# Wire_Puzzle.net
KiCad netlist of a schematic drawn in EAGLE
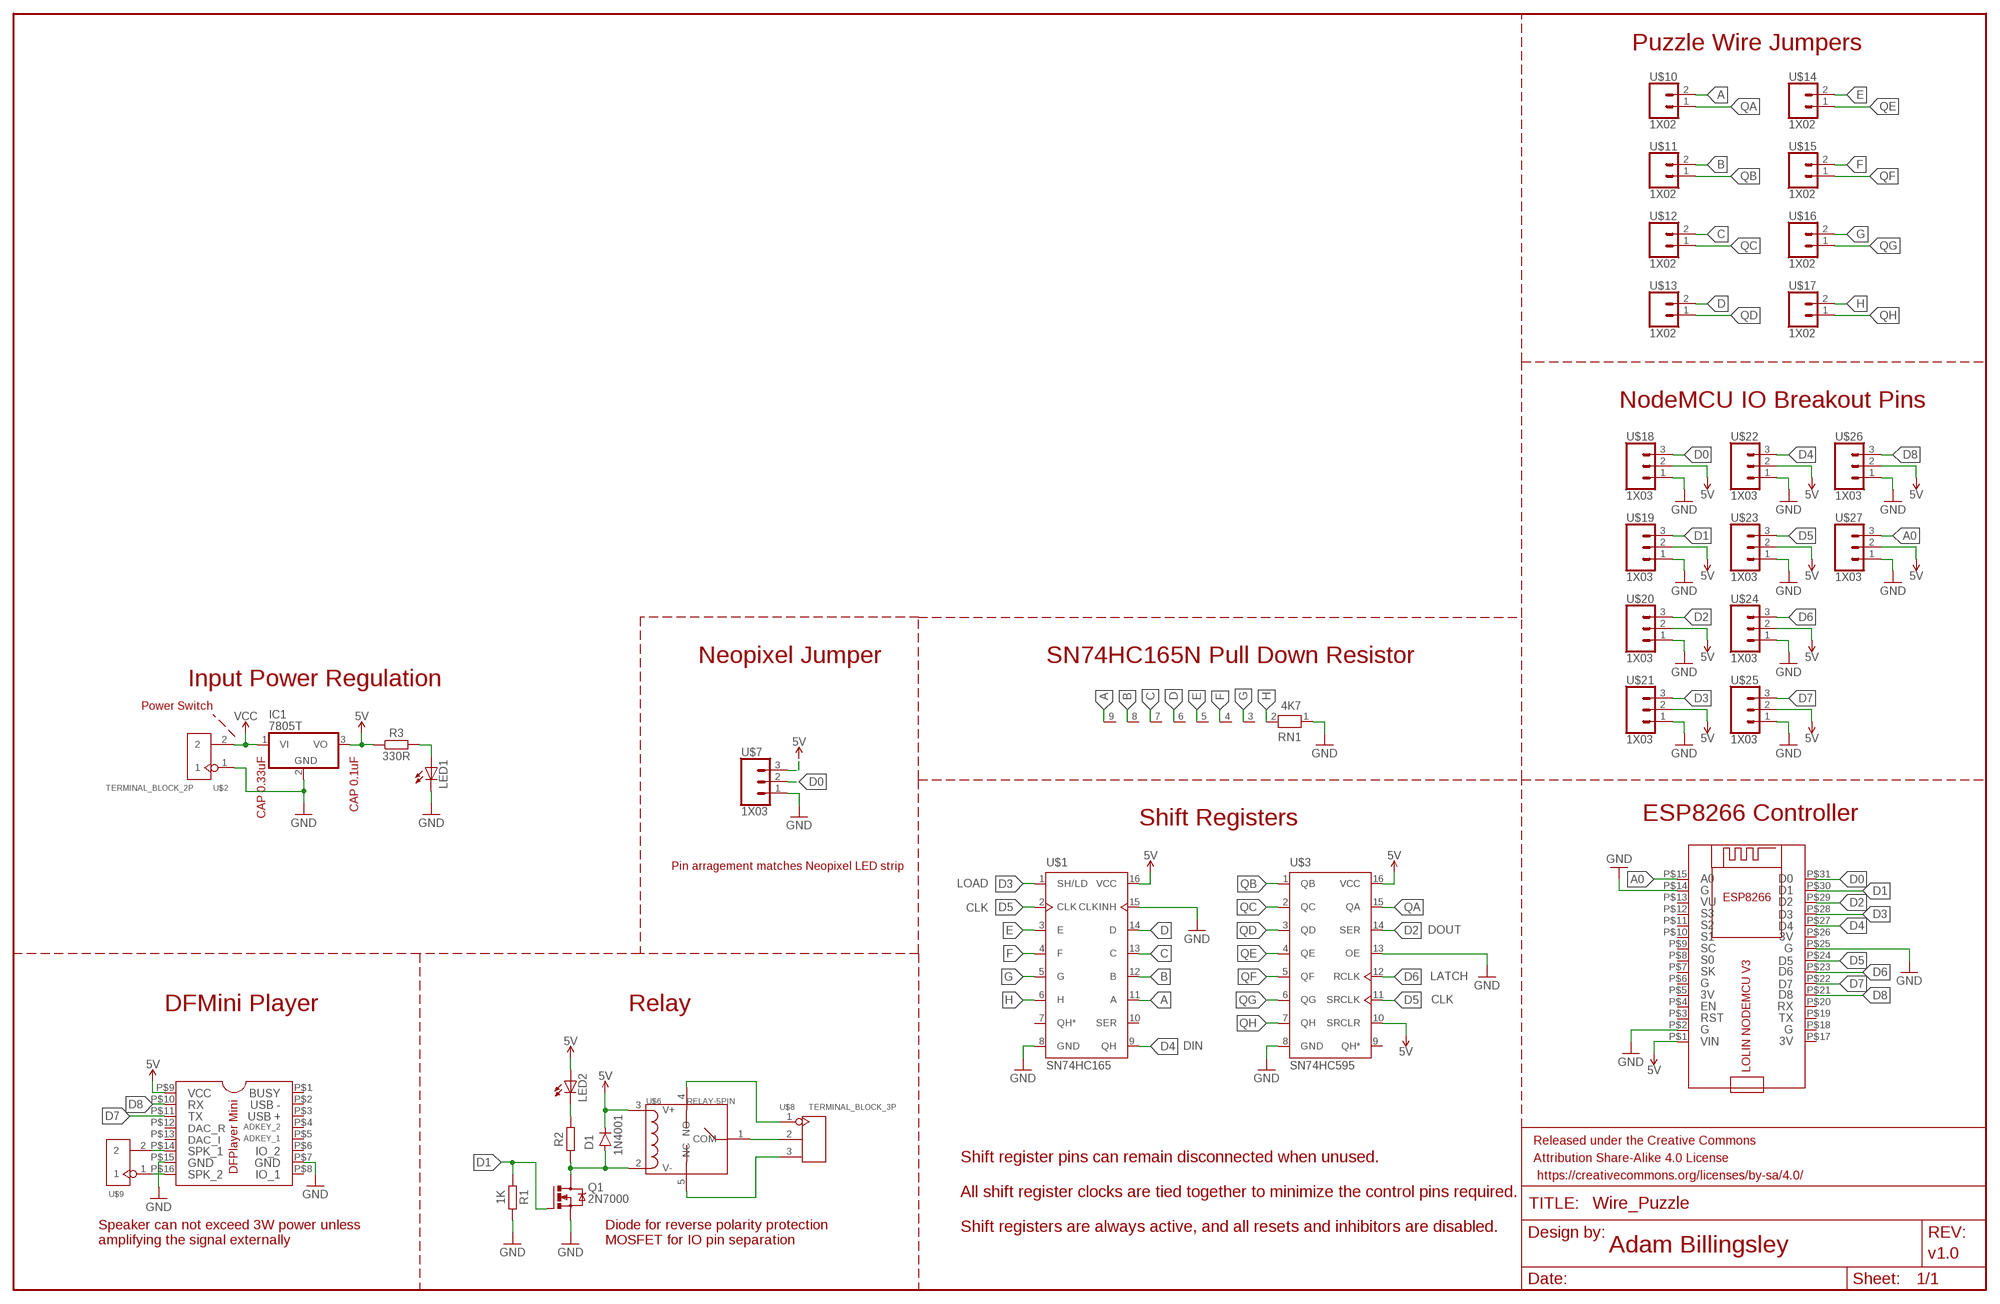
[diagram p0: schematic, sheet 1]

(export (version "E")
  (design (tool "Eeschema 10.0.6"))
  (components
    (comp (ref "D1")
      (value "1N4001")
      (footprint "eagle-import:DO-41")
      (fields
        (field (name "DIGIKEY_PART_NUMBER") "1N4004MSCT-ND")
        (field (name "MANUFACTURER") "Micro Commercial Co")
        (field (name "MPN") "1N4004")
        (field (name "CREATED_BY") "PCBLayout.com")
      )
      (libsource (lib "eagle-import") (part "1N4004"))
    )
    (comp (ref "FRAME1")
      (value "FRAME-LEDGER")
      (footprint "eagle-import:CREATIVE_COMMONS")
      (libsource (lib "eagle-import") (part "FRAME-LEDGER"))
    )
    (comp (ref "IC1")
      (value "7805T")
      (footprint "eagle-import:TO220H")
      (libsource (lib "eagle-import") (part "78T05"))
    )
    (comp (ref "LED1")
      (value "LED5MM")
      (footprint "eagle-import:LED5MM")
      (libsource (lib "eagle-import") (part "LED5MM"))
    )
    (comp (ref "LED2")
      (value "LED5MM")
      (footprint "eagle-import:LED5MM")
      (libsource (lib "eagle-import") (part "LED5MM"))
    )
    (comp (ref "Q1")
      (value "2N7000")
      (footprint "eagle-import:TO92")
      (libsource (lib "eagle-import") (part "NMOSFET_TO92_"))
    )
    (comp (ref "R1")
      (value "1K")
      (footprint "eagle-import:RESAD724W46L381D178B")
      (libsource (lib "eagle-import") (part "RAXIAL-7.2MM-PITCH_"))
    )
    (comp (ref "R2")
      (value "R_AXIAL-7.2MM-PITCH")
      (footprint "eagle-import:RESAD724W46L381D178B")
      (libsource (lib "eagle-import") (part "RAXIAL-7.2MM-PITCH_"))
    )
    (comp (ref "R3")
      (value "330R")
      (footprint "eagle-import:RESAD724W46L381D178B")
      (libsource (lib "eagle-import") (part "RAXIAL-7.2MM-PITCH_"))
    )
    (comp (ref "RN1")
      (value "4K7")
      (footprint "eagle-import:RN-9")
      (libsource (lib "eagle-import") (part "RN08"))
    )
    (comp (ref "U$1")
      (value "SN74HC165")
      (footprint "eagle-import:DIL16")
      (libsource (lib "eagle-import") (part "SN74HC165"))
    )
    (comp (ref "U$2")
      (value "TERMINAL_BLOCK_2P")
      (footprint "eagle-import:H2-5.0-10.5X8.0MM")
      (libsource (lib "eagle-import") (part "TERMINAL_BLOCK_2P"))
    )
    (comp (ref "U$3")
      (value "SN74HC595")
      (footprint "eagle-import:DIL16")
      (libsource (lib "eagle-import") (part "SN74HC595"))
    )
    (comp (ref "U$4")
      (value "LOLIN_NODEMCU")
      (footprint "eagle-import:LOLIN_NODEMCU")
      (libsource (lib "eagle-import") (part "LOLIN_NODEMCU"))
    )
    (comp (ref "U$5")
      (value "DFPLAYER_MINI")
      (footprint "eagle-import:DFMINI")
      (libsource (lib "eagle-import") (part "DFPLAYER_MINI"))
    )
    (comp (ref "U$6")
      (value "RELAY-5PIN")
      (footprint "eagle-import:RELAY-19.0X15.0X15.0MM")
      (libsource (lib "eagle-import") (part "RELAY-5PIN"))
    )
    (comp (ref "U$7")
      (value "1X03")
      (footprint "eagle-import:1X03")
      (libsource (lib "eagle-import") (part "1X03"))
    )
    (comp (ref "U$8")
      (value "TERMINAL_BLOCK_3P")
      (footprint "eagle-import:H3-5.0-15.5X8.0MM")
      (libsource (lib "eagle-import") (part "TERMINAL_BLOCK_3P"))
    )
    (comp (ref "U$9")
      (value "TERMINAL_BLOCK_2P")
      (footprint "eagle-import:H2-5.0-10.5X8.0MM")
      (libsource (lib "eagle-import") (part "TERMINAL_BLOCK_2P"))
    )
    (comp (ref "U$10")
      (value "1X02")
      (footprint "eagle-import:1X02")
      (libsource (lib "eagle-import") (part "1X02"))
    )
    (comp (ref "U$11")
      (value "1X02")
      (footprint "eagle-import:1X02")
      (libsource (lib "eagle-import") (part "1X02"))
    )
    (comp (ref "U$12")
      (value "1X02")
      (footprint "eagle-import:1X02")
      (libsource (lib "eagle-import") (part "1X02"))
    )
    (comp (ref "U$13")
      (value "1X02")
      (footprint "eagle-import:1X02")
      (libsource (lib "eagle-import") (part "1X02"))
    )
    (comp (ref "U$14")
      (value "1X02")
      (footprint "eagle-import:1X02")
      (libsource (lib "eagle-import") (part "1X02"))
    )
    (comp (ref "U$15")
      (value "1X02")
      (footprint "eagle-import:1X02")
      (libsource (lib "eagle-import") (part "1X02"))
    )
    (comp (ref "U$16")
      (value "1X02")
      (footprint "eagle-import:1X02")
      (libsource (lib "eagle-import") (part "1X02"))
    )
    (comp (ref "U$17")
      (value "1X02")
      (footprint "eagle-import:1X02")
      (libsource (lib "eagle-import") (part "1X02"))
    )
    (comp (ref "U$18")
      (value "1X03")
      (footprint "eagle-import:1X03")
      (libsource (lib "eagle-import") (part "1X03"))
    )
    (comp (ref "U$19")
      (value "1X03")
      (footprint "eagle-import:1X03")
      (libsource (lib "eagle-import") (part "1X03"))
    )
    (comp (ref "U$20")
      (value "1X03")
      (footprint "eagle-import:1X03")
      (libsource (lib "eagle-import") (part "1X03"))
    )
    (comp (ref "U$21")
      (value "1X03")
      (footprint "eagle-import:1X03")
      (libsource (lib "eagle-import") (part "1X03"))
    )
    (comp (ref "U$22")
      (value "1X03")
      (footprint "eagle-import:1X03")
      (libsource (lib "eagle-import") (part "1X03"))
    )
    (comp (ref "U$23")
      (value "1X03")
      (footprint "eagle-import:1X03")
      (libsource (lib "eagle-import") (part "1X03"))
    )
    (comp (ref "U$24")
      (value "1X03")
      (footprint "eagle-import:1X03")
      (libsource (lib "eagle-import") (part "1X03"))
    )
    (comp (ref "U$25")
      (value "1X03")
      (footprint "eagle-import:1X03")
      (libsource (lib "eagle-import") (part "1X03"))
    )
    (comp (ref "U$26")
      (value "1X03")
      (footprint "eagle-import:1X03")
      (libsource (lib "eagle-import") (part "1X03"))
    )
    (comp (ref "U$27")
      (value "1X03")
      (footprint "eagle-import:1X03")
      (libsource (lib "eagle-import") (part "1X03"))
    )
  )
  (nets
    (net (code "1") (name "/3V_1") (class "Default")
      (node (ref "U$4") (pin "P$5") (pinfunction "3V_1_P$5") (pintype "power_in"))
    )
    (net (code "2") (name "/3V_2") (class "Default")
      (node (ref "U$4") (pin "P$17") (pinfunction "3V_2_P$17") (pintype "power_in"))
    )
    (net (code "3") (name "/3V_3") (class "Default")
      (node (ref "U$4") (pin "P$26") (pinfunction "3V_3_P$26") (pintype "power_in"))
    )
    (net (code "4") (name "/G_2") (class "Default")
      (node (ref "U$4") (pin "P$6") (pinfunction "G_2_P$6") (pintype "power_in"))
    )
    (net (code "5") (name "/G_4") (class "Default")
      (node (ref "U$4") (pin "P$18") (pinfunction "G_4_P$18") (pintype "power_in"))
    )
    (net (code "6") (name "/VU") (class "Default")
      (node (ref "U$4") (pin "P$13") (pinfunction "VU_P$13") (pintype "power_in"))
    )
    (net (code "7") (name "5V") (class "Default")
      (node (ref "D1") (pin "C") (pinfunction "C_C") (pintype "passive"))
      (node (ref "IC1") (pin "3") (pinfunction "VO_3") (pintype "passive"))
      (node (ref "LED2") (pin "A") (pinfunction "A_A") (pintype "passive"))
      (node (ref "R3") (pin "1") (pinfunction "1_1") (pintype "passive"))
      (node (ref "U$1") (pin "16") (pinfunction "VCC_16") (pintype "power_in"))
      (node (ref "U$18") (pin "2") (pinfunction "2_2") (pintype "passive"))
      (node (ref "U$19") (pin "2") (pinfunction "2_2") (pintype "passive"))
      (node (ref "U$20") (pin "2") (pinfunction "2_2") (pintype "passive"))
      (node (ref "U$21") (pin "2") (pinfunction "2_2") (pintype "passive"))
      (node (ref "U$22") (pin "2") (pinfunction "2_2") (pintype "passive"))
      (node (ref "U$23") (pin "2") (pinfunction "2_2") (pintype "passive"))
      (node (ref "U$24") (pin "2") (pinfunction "2_2") (pintype "passive"))
      (node (ref "U$25") (pin "2") (pinfunction "2_2") (pintype "passive"))
      (node (ref "U$26") (pin "2") (pinfunction "2_2") (pintype "passive"))
      (node (ref "U$27") (pin "2") (pinfunction "2_2") (pintype "passive"))
      (node (ref "U$3") (pin "10") (pinfunction "SRCLR_10") (pintype "open_collector"))
      (node (ref "U$3") (pin "16") (pinfunction "VCC_16") (pintype "power_in"))
      (node (ref "U$4") (pin "P$1") (pinfunction "VIN_P$1") (pintype "power_in"))
      (node (ref "U$5") (pin "P$9") (pinfunction "P$9_P$9") (pintype "power_in"))
      (node (ref "U$6") (pin "3") (pinfunction "V+_3") (pintype "bidirectional"))
      (node (ref "U$7") (pin "3") (pinfunction "3_3") (pintype "passive"))
    )
    (net (code "8") (name "A") (class "Default")
      (node (ref "RN1") (pin "9") (pinfunction "9_9") (pintype "passive"))
      (node (ref "U$1") (pin "11") (pinfunction "A_11") (pintype "input"))
      (node (ref "U$10") (pin "2") (pinfunction "2_2") (pintype "passive"))
    )
    (net (code "9") (name "A0") (class "Default")
      (node (ref "U$27") (pin "3") (pinfunction "3_3") (pintype "passive"))
      (node (ref "U$4") (pin "P$15") (pinfunction "A0_P$15") (pintype "bidirectional"))
    )
    (net (code "10") (name "B") (class "Default")
      (node (ref "RN1") (pin "8") (pinfunction "8_8") (pintype "passive"))
      (node (ref "U$1") (pin "12") (pinfunction "B_12") (pintype "input"))
      (node (ref "U$11") (pin "2") (pinfunction "2_2") (pintype "passive"))
    )
    (net (code "11") (name "C") (class "Default")
      (node (ref "RN1") (pin "7") (pinfunction "7_7") (pintype "passive"))
      (node (ref "U$1") (pin "13") (pinfunction "C_13") (pintype "input"))
      (node (ref "U$12") (pin "2") (pinfunction "2_2") (pintype "passive"))
    )
    (net (code "12") (name "D") (class "Default")
      (node (ref "RN1") (pin "6") (pinfunction "6_6") (pintype "passive"))
      (node (ref "U$1") (pin "14") (pinfunction "D_14") (pintype "input"))
      (node (ref "U$13") (pin "2") (pinfunction "2_2") (pintype "passive"))
    )
    (net (code "13") (name "D0") (class "Default")
      (node (ref "U$18") (pin "3") (pinfunction "3_3") (pintype "passive"))
      (node (ref "U$4") (pin "P$31") (pinfunction "D0_P$31") (pintype "bidirectional"))
      (node (ref "U$7") (pin "2") (pinfunction "2_2") (pintype "passive"))
    )
    (net (code "14") (name "D1") (class "Default")
      (node (ref "Q1") (pin "2") (pinfunction "G_2") (pintype "passive"))
      (node (ref "R1") (pin "1") (pinfunction "1_1") (pintype "passive"))
      (node (ref "U$19") (pin "3") (pinfunction "3_3") (pintype "passive"))
      (node (ref "U$4") (pin "P$30") (pinfunction "D1_P$30") (pintype "bidirectional"))
    )
    (net (code "15") (name "D2") (class "Default")
      (node (ref "U$20") (pin "3") (pinfunction "3_3") (pintype "passive"))
      (node (ref "U$3") (pin "14") (pinfunction "SER_14") (pintype "input"))
      (node (ref "U$4") (pin "P$29") (pinfunction "D2_P$29") (pintype "bidirectional"))
    )
    (net (code "16") (name "D3") (class "Default")
      (node (ref "U$1") (pin "1") (pinfunction "SH/LD_1") (pintype "open_collector"))
      (node (ref "U$21") (pin "3") (pinfunction "3_3") (pintype "passive"))
      (node (ref "U$4") (pin "P$28") (pinfunction "D3_P$28") (pintype "bidirectional"))
    )
    (net (code "17") (name "D4") (class "Default")
      (node (ref "U$1") (pin "9") (pinfunction "QH_9") (pintype "output"))
      (node (ref "U$22") (pin "3") (pinfunction "3_3") (pintype "passive"))
      (node (ref "U$4") (pin "P$27") (pinfunction "D4_P$27") (pintype "bidirectional"))
    )
    (net (code "18") (name "D5") (class "Default")
      (node (ref "U$1") (pin "2") (pinfunction "CLK_2") (pintype "input"))
      (node (ref "U$23") (pin "3") (pinfunction "3_3") (pintype "passive"))
      (node (ref "U$3") (pin "11") (pinfunction "SRCLK_11") (pintype "input"))
      (node (ref "U$4") (pin "P$24") (pinfunction "D5_P$24") (pintype "bidirectional"))
    )
    (net (code "19") (name "D6") (class "Default")
      (node (ref "U$24") (pin "3") (pinfunction "3_3") (pintype "passive"))
      (node (ref "U$3") (pin "12") (pinfunction "RCLK_12") (pintype "input"))
      (node (ref "U$4") (pin "P$23") (pinfunction "D6_P$23") (pintype "bidirectional"))
    )
    (net (code "20") (name "D7") (class "Default")
      (node (ref "U$25") (pin "3") (pinfunction "3_3") (pintype "passive"))
      (node (ref "U$4") (pin "P$22") (pinfunction "D7_P$22") (pintype "bidirectional"))
      (node (ref "U$5") (pin "P$11") (pinfunction "P$11_P$11") (pintype "bidirectional"))
    )
    (net (code "21") (name "D8") (class "Default")
      (node (ref "U$26") (pin "3") (pinfunction "3_3") (pintype "passive"))
      (node (ref "U$4") (pin "P$21") (pinfunction "D8_P$21") (pintype "bidirectional"))
      (node (ref "U$5") (pin "P$10") (pinfunction "P$10_P$10") (pintype "bidirectional"))
    )
    (net (code "22") (name "E") (class "Default")
      (node (ref "RN1") (pin "5") (pinfunction "5_5") (pintype "passive"))
      (node (ref "U$1") (pin "3") (pinfunction "E_3") (pintype "input"))
      (node (ref "U$14") (pin "2") (pinfunction "2_2") (pintype "passive"))
    )
    (net (code "23") (name "F") (class "Default")
      (node (ref "RN1") (pin "4") (pinfunction "4_4") (pintype "passive"))
      (node (ref "U$1") (pin "4") (pinfunction "F_4") (pintype "input"))
      (node (ref "U$15") (pin "2") (pinfunction "2_2") (pintype "passive"))
    )
    (net (code "24") (name "G") (class "Default")
      (node (ref "RN1") (pin "3") (pinfunction "3_3") (pintype "passive"))
      (node (ref "U$1") (pin "5") (pinfunction "G_5") (pintype "input"))
      (node (ref "U$16") (pin "2") (pinfunction "2_2") (pintype "passive"))
    )
    (net (code "25") (name "GND") (class "Default")
      (node (ref "IC1") (pin "2") (pinfunction "GND_2") (pintype "passive"))
      (node (ref "LED1") (pin "K") (pinfunction "C_K") (pintype "passive"))
      (node (ref "Q1") (pin "3") (pinfunction "S_3") (pintype "passive"))
      (node (ref "R1") (pin "2") (pinfunction "2_2") (pintype "passive"))
      (node (ref "RN1") (pin "1") (pinfunction "1_1") (pintype "passive"))
      (node (ref "U$1") (pin "15") (pinfunction "CLKINH_15") (pintype "input"))
      (node (ref "U$1") (pin "8") (pinfunction "GND_8") (pintype "power_in"))
      (node (ref "U$18") (pin "1") (pinfunction "1_1") (pintype "passive"))
      (node (ref "U$19") (pin "1") (pinfunction "1_1") (pintype "passive"))
      (node (ref "U$2") (pin "1") (pinfunction "1_1") (pintype "bidirectional"))
      (node (ref "U$20") (pin "1") (pinfunction "1_1") (pintype "passive"))
      (node (ref "U$21") (pin "1") (pinfunction "1_1") (pintype "passive"))
      (node (ref "U$22") (pin "1") (pinfunction "1_1") (pintype "passive"))
      (node (ref "U$23") (pin "1") (pinfunction "1_1") (pintype "passive"))
      (node (ref "U$24") (pin "1") (pinfunction "1_1") (pintype "passive"))
      (node (ref "U$25") (pin "1") (pinfunction "1_1") (pintype "passive"))
      (node (ref "U$26") (pin "1") (pinfunction "1_1") (pintype "passive"))
      (node (ref "U$27") (pin "1") (pinfunction "1_1") (pintype "passive"))
      (node (ref "U$3") (pin "13") (pinfunction "OE_13") (pintype "open_collector"))
      (node (ref "U$3") (pin "8") (pinfunction "GND_8") (pintype "power_in"))
      (node (ref "U$4") (pin "P$14") (pinfunction "G_3_P$14") (pintype "power_in"))
      (node (ref "U$4") (pin "P$2") (pinfunction "G_1_P$2") (pintype "power_in"))
      (node (ref "U$4") (pin "P$25") (pinfunction "G_5_P$25") (pintype "power_in"))
      (node (ref "U$5") (pin "P$15") (pinfunction "P$15_P$15") (pintype "power_in"))
      (node (ref "U$5") (pin "P$7") (pinfunction "P$7_P$7") (pintype "power_in"))
      (node (ref "U$7") (pin "1") (pinfunction "1_1") (pintype "passive"))
    )
    (net (code "26") (name "H") (class "Default")
      (node (ref "RN1") (pin "2") (pinfunction "2_2") (pintype "passive"))
      (node (ref "U$1") (pin "6") (pinfunction "H_6") (pintype "input"))
      (node (ref "U$17") (pin "2") (pinfunction "2_2") (pintype "passive"))
    )
    (net (code "27") (name "Net-(LED1-PadA)") (class "Default")
      (node (ref "LED1") (pin "A") (pinfunction "A_A") (pintype "passive"))
      (node (ref "R3") (pin "2") (pinfunction "2_2") (pintype "passive"))
    )
    (net (code "28") (name "Net-(LED2-C)") (class "Default")
      (node (ref "LED2") (pin "K") (pinfunction "C_K") (pintype "passive"))
      (node (ref "R2") (pin "2") (pinfunction "2_2") (pintype "passive"))
    )
    (net (code "29") (name "Net-(Q1-D)") (class "Default")
      (node (ref "D1") (pin "A") (pinfunction "A_A") (pintype "passive"))
      (node (ref "Q1") (pin "1") (pinfunction "D_1") (pintype "passive"))
      (node (ref "R2") (pin "1") (pinfunction "1_1") (pintype "passive"))
      (node (ref "U$6") (pin "2") (pinfunction "V-_2") (pintype "bidirectional"))
    )
    (net (code "30") (name "Net-(U$5-PadP$14)") (class "Default")
      (node (ref "U$5") (pin "P$14") (pinfunction "P$14_P$14") (pintype "bidirectional"))
      (node (ref "U$9") (pin "2") (pinfunction "2_2") (pintype "bidirectional"))
    )
    (net (code "31") (name "Net-(U$5-PadP$16)") (class "Default")
      (node (ref "U$5") (pin "P$16") (pinfunction "P$16_P$16") (pintype "bidirectional"))
      (node (ref "U$9") (pin "1") (pinfunction "1_1") (pintype "bidirectional"))
    )
    (net (code "32") (name "Net-(U$6-COM)") (class "Default")
      (node (ref "U$6") (pin "1") (pinfunction "COM_1") (pintype "bidirectional"))
      (node (ref "U$8") (pin "2") (pinfunction "P$2_2") (pintype "bidirectional"))
    )
    (net (code "33") (name "Net-(U$6-NC)") (class "Default")
      (node (ref "U$6") (pin "5") (pinfunction "NC_5") (pintype "bidirectional"))
      (node (ref "U$8") (pin "3") (pinfunction "P$3_3") (pintype "bidirectional"))
    )
    (net (code "34") (name "Net-(U$6-NO)") (class "Default")
      (node (ref "U$6") (pin "4") (pinfunction "NO_4") (pintype "bidirectional"))
      (node (ref "U$8") (pin "1") (pinfunction "P$1_1") (pintype "bidirectional"))
    )
    (net (code "35") (name "QA") (class "Default")
      (node (ref "U$10") (pin "1") (pinfunction "1_1") (pintype "passive"))
      (node (ref "U$3") (pin "15") (pinfunction "QA_15") (pintype "output"))
    )
    (net (code "36") (name "QB") (class "Default")
      (node (ref "U$11") (pin "1") (pinfunction "1_1") (pintype "passive"))
      (node (ref "U$3") (pin "1") (pinfunction "QB_1") (pintype "output"))
    )
    (net (code "37") (name "QC") (class "Default")
      (node (ref "U$12") (pin "1") (pinfunction "1_1") (pintype "passive"))
      (node (ref "U$3") (pin "2") (pinfunction "QC_2") (pintype "output"))
    )
    (net (code "38") (name "QD") (class "Default")
      (node (ref "U$13") (pin "1") (pinfunction "1_1") (pintype "passive"))
      (node (ref "U$3") (pin "3") (pinfunction "QD_3") (pintype "output"))
    )
    (net (code "39") (name "QE") (class "Default")
      (node (ref "U$14") (pin "1") (pinfunction "1_1") (pintype "passive"))
      (node (ref "U$3") (pin "4") (pinfunction "QE_4") (pintype "output"))
    )
    (net (code "40") (name "QF") (class "Default")
      (node (ref "U$15") (pin "1") (pinfunction "1_1") (pintype "passive"))
      (node (ref "U$3") (pin "5") (pinfunction "QF_5") (pintype "output"))
    )
    (net (code "41") (name "QG") (class "Default")
      (node (ref "U$16") (pin "1") (pinfunction "1_1") (pintype "passive"))
      (node (ref "U$3") (pin "6") (pinfunction "QG_6") (pintype "output"))
    )
    (net (code "42") (name "QH") (class "Default")
      (node (ref "U$17") (pin "1") (pinfunction "1_1") (pintype "passive"))
      (node (ref "U$3") (pin "7") (pinfunction "QH_7") (pintype "output"))
    )
    (net (code "43") (name "VCC") (class "Default")
      (node (ref "IC1") (pin "1") (pinfunction "VI_1") (pintype "input"))
      (node (ref "U$2") (pin "2") (pinfunction "2_2") (pintype "bidirectional"))
    )
    (net (code "44") (name "unconnected-(U$1-QH*-Pad7)") (class "Default")
      (node (ref "U$1") (pin "7") (pinfunction "QH*_7") (pintype "output"))
    )
    (net (code "45") (name "unconnected-(U$1-SER-Pad10)") (class "Default")
      (node (ref "U$1") (pin "10") (pinfunction "SER_10") (pintype "input"))
    )
    (net (code "46") (name "unconnected-(U$3-QH*-Pad9)") (class "Default")
      (node (ref "U$3") (pin "9") (pinfunction "QH*_9") (pintype "output"))
    )
    (net (code "47") (name "unconnected-(U$4-EN-PadP$4)") (class "Default")
      (node (ref "U$4") (pin "P$4") (pinfunction "EN_P$4") (pintype "input"))
    )
    (net (code "48") (name "unconnected-(U$4-RST-PadP$3)") (class "Default")
      (node (ref "U$4") (pin "P$3") (pinfunction "RST_P$3") (pintype "input"))
    )
    (net (code "49") (name "unconnected-(U$4-RX-PadP$20)") (class "Default")
      (node (ref "U$4") (pin "P$20") (pinfunction "RX_P$20") (pintype "input"))
    )
    (net (code "50") (name "unconnected-(U$4-S0-PadP$8)") (class "Default")
      (node (ref "U$4") (pin "P$8") (pinfunction "S0_P$8") (pintype "bidirectional"))
    )
    (net (code "51") (name "unconnected-(U$4-S1-PadP$10)") (class "Default")
      (node (ref "U$4") (pin "P$10") (pinfunction "S1_P$10") (pintype "bidirectional"))
    )
    (net (code "52") (name "unconnected-(U$4-S2-PadP$11)") (class "Default")
      (node (ref "U$4") (pin "P$11") (pinfunction "S2_P$11") (pintype "bidirectional"))
    )
    (net (code "53") (name "unconnected-(U$4-S3-PadP$12)") (class "Default")
      (node (ref "U$4") (pin "P$12") (pinfunction "S3_P$12") (pintype "bidirectional"))
    )
    (net (code "54") (name "unconnected-(U$4-SC-PadP$9)") (class "Default")
      (node (ref "U$4") (pin "P$9") (pinfunction "SC_P$9") (pintype "bidirectional"))
    )
    (net (code "55") (name "unconnected-(U$4-SK-PadP$7)") (class "Default")
      (node (ref "U$4") (pin "P$7") (pinfunction "SK_P$7") (pintype "bidirectional"))
    )
    (net (code "56") (name "unconnected-(U$4-TX-PadP$19)") (class "Default")
      (node (ref "U$4") (pin "P$19") (pinfunction "TX_P$19") (pintype "output"))
    )
    (net (code "57") (name "unconnected-(U$5-PadP$1)") (class "Default")
      (node (ref "U$5") (pin "P$1") (pinfunction "P$1_P$1") (pintype "bidirectional"))
    )
    (net (code "58") (name "unconnected-(U$5-PadP$2)") (class "Default")
      (node (ref "U$5") (pin "P$2") (pinfunction "P$2_P$2") (pintype "bidirectional"))
    )
    (net (code "59") (name "unconnected-(U$5-PadP$3)") (class "Default")
      (node (ref "U$5") (pin "P$3") (pinfunction "P$3_P$3") (pintype "bidirectional"))
    )
    (net (code "60") (name "unconnected-(U$5-PadP$4)") (class "Default")
      (node (ref "U$5") (pin "P$4") (pinfunction "P$4_P$4") (pintype "bidirectional"))
    )
    (net (code "61") (name "unconnected-(U$5-PadP$5)") (class "Default")
      (node (ref "U$5") (pin "P$5") (pinfunction "P$5_P$5") (pintype "bidirectional"))
    )
    (net (code "62") (name "unconnected-(U$5-PadP$6)") (class "Default")
      (node (ref "U$5") (pin "P$6") (pinfunction "P$6_P$6") (pintype "bidirectional"))
    )
    (net (code "63") (name "unconnected-(U$5-PadP$8)") (class "Default")
      (node (ref "U$5") (pin "P$8") (pinfunction "P$8_P$8") (pintype "bidirectional"))
    )
    (net (code "64") (name "unconnected-(U$5-PadP$12)") (class "Default")
      (node (ref "U$5") (pin "P$12") (pinfunction "P$12_P$12") (pintype "bidirectional"))
    )
    (net (code "65") (name "unconnected-(U$5-PadP$13)") (class "Default")
      (node (ref "U$5") (pin "P$13") (pinfunction "P$13_P$13") (pintype "bidirectional"))
    )
  )
)
